# fan_2024-11-08_no1.net
KiCad netlist of a schematic drawn in EasyEDA Pro
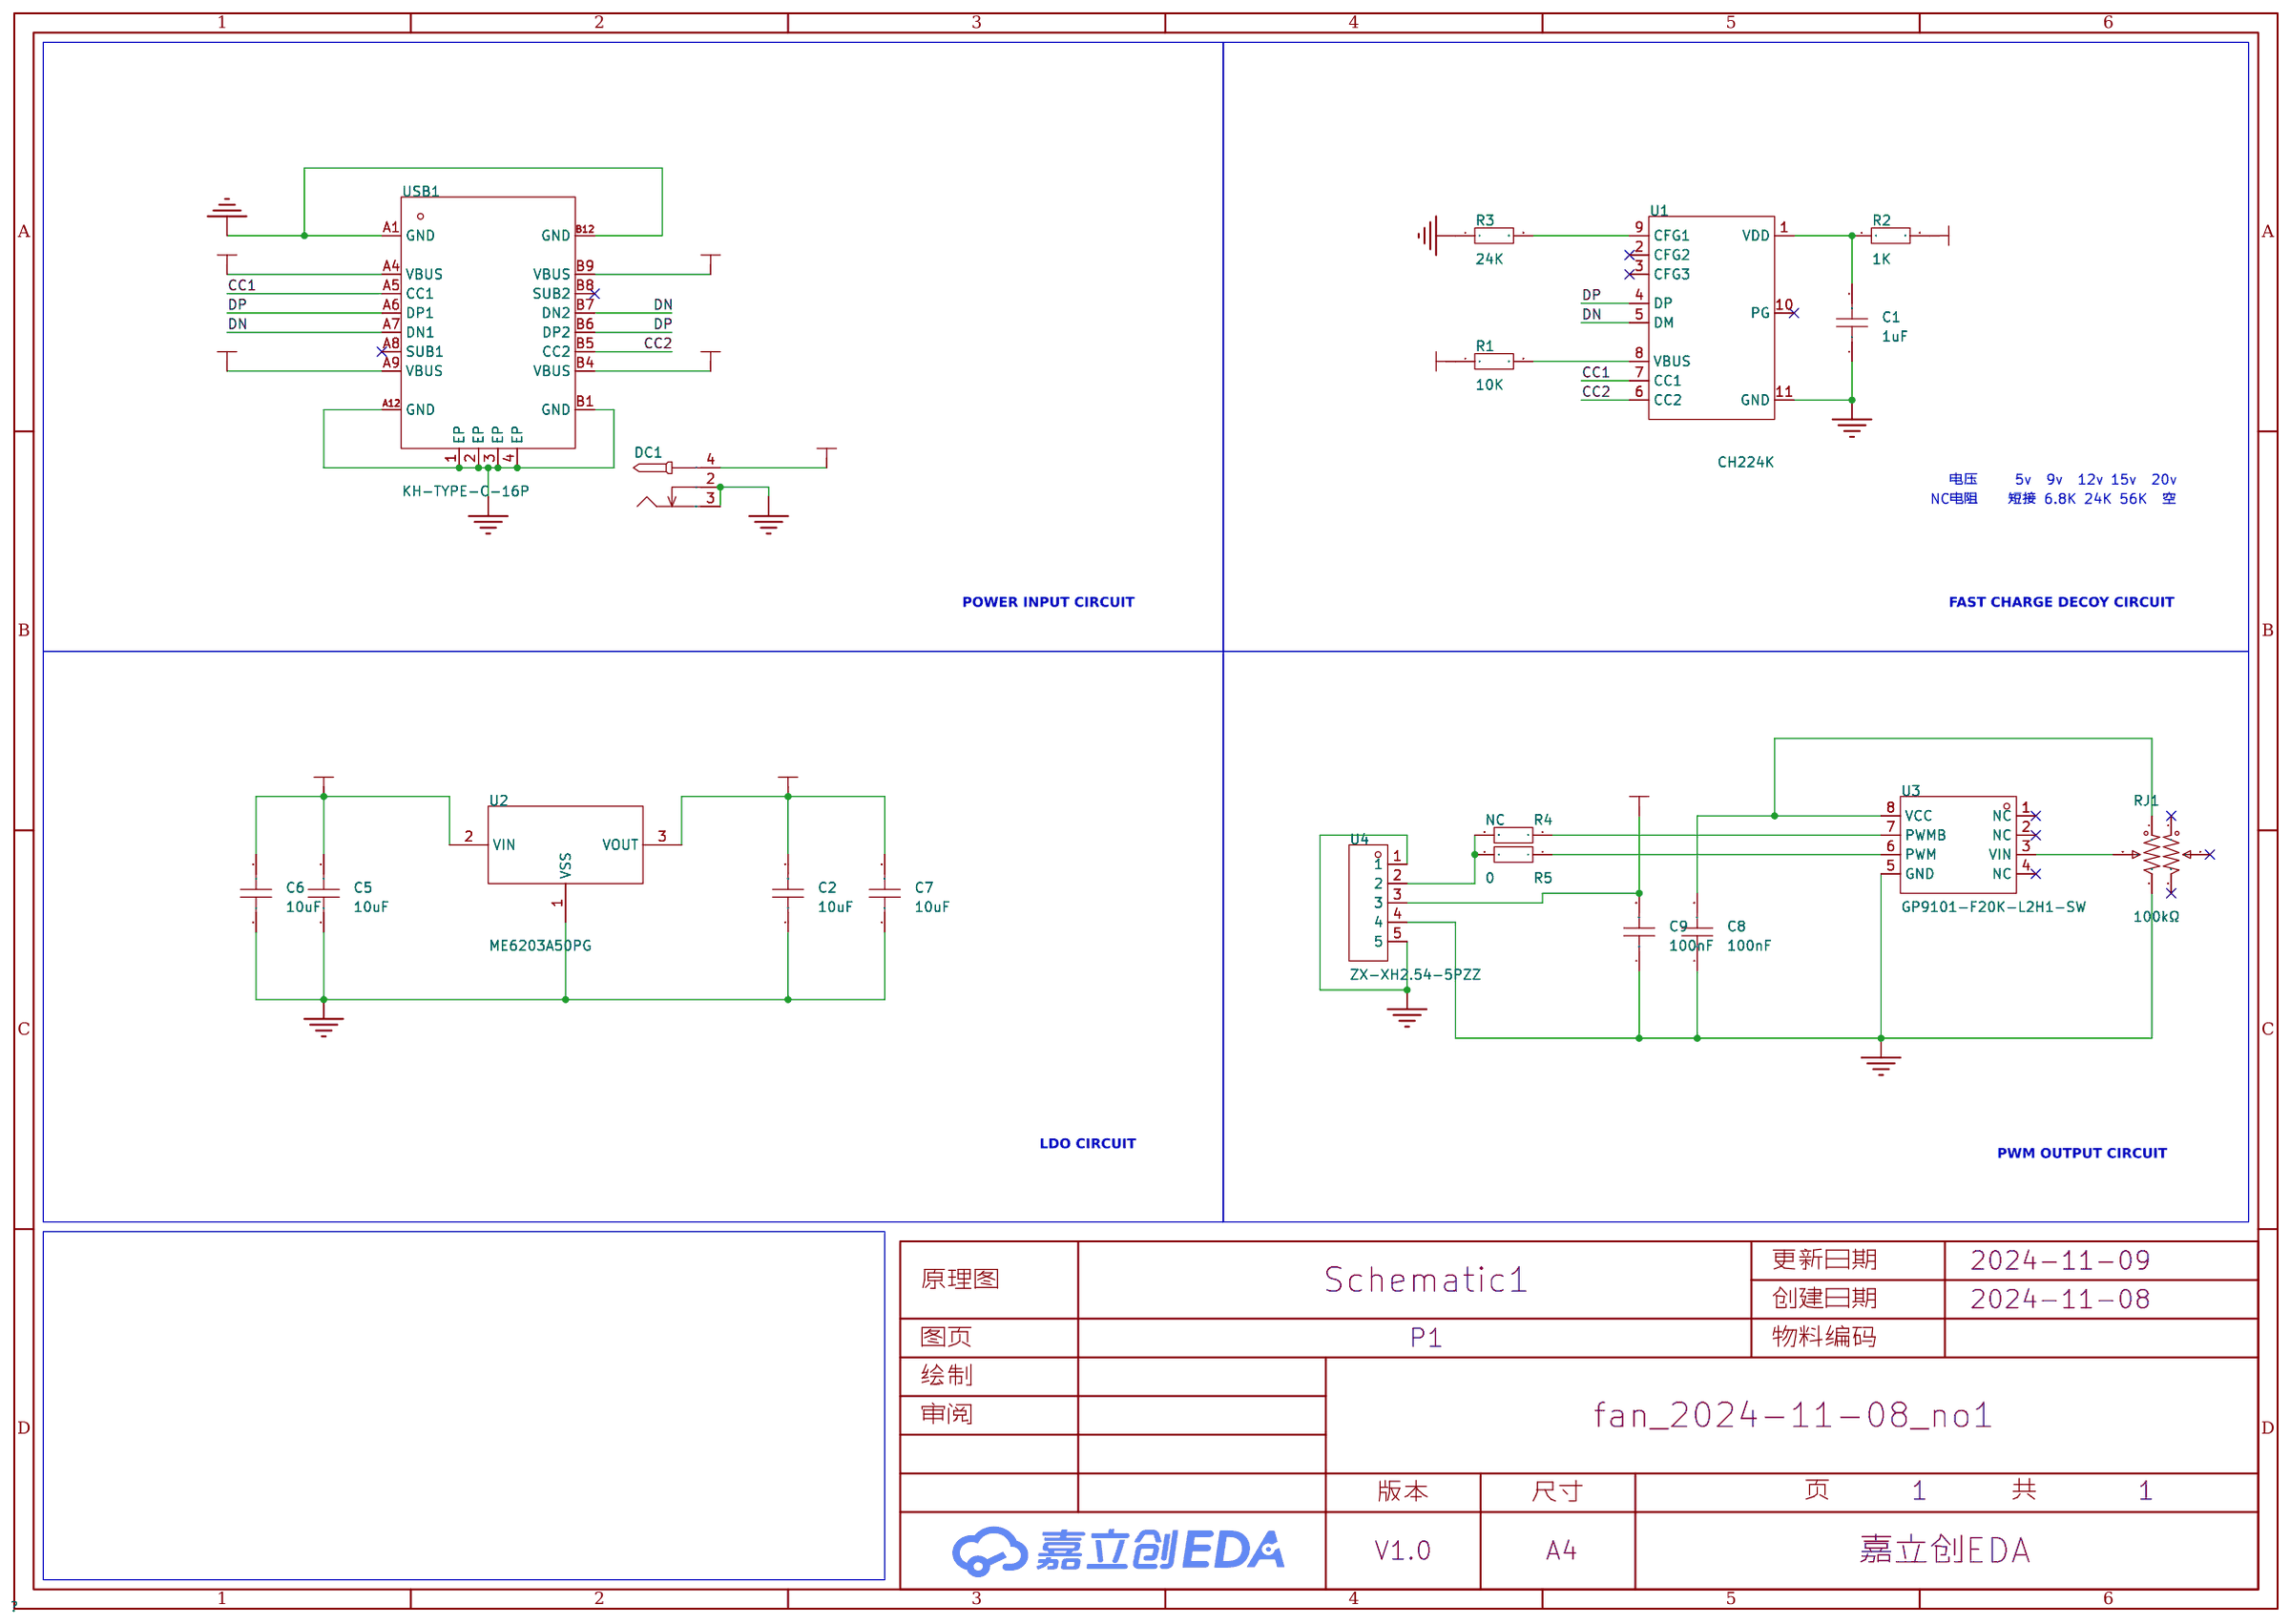
[diagram p0: schematic sheet]

(export (version "E")
  (design (tool "Eeschema 10.0.6"))
  (components
    (comp (ref "C1")
      (value "1uF")
      (footprint "easyedapro:C0603")
      (libsource (lib "easyedapro") (part "CapAcitance"))
    )
    (comp (ref "C2")
      (value "10uF")
      (footprint "easyedapro:C0603")
      (libsource (lib "easyedapro") (part "CapAcitance"))
    )
    (comp (ref "C5")
      (value "10uF")
      (footprint "easyedapro:C0603")
      (libsource (lib "easyedapro") (part "CapAcitance"))
    )
    (comp (ref "C6")
      (value "10uF")
      (footprint "easyedapro:C0603")
      (libsource (lib "easyedapro") (part "CapAcitance"))
    )
    (comp (ref "C7")
      (value "10uF")
      (footprint "easyedapro:C0603")
      (libsource (lib "easyedapro") (part "CapAcitance"))
    )
    (comp (ref "C8")
      (value "100nF")
      (footprint "easyedapro:C0603")
      (libsource (lib "easyedapro") (part "CapAcitance"))
    )
    (comp (ref "C9")
      (value "100nF")
      (footprint "easyedapro:C0603")
      (libsource (lib "easyedapro") (part "CapAcitance"))
    )
    (comp (ref "DC1")
      (value "~")
      (footprint "easyedapro:DC-2.0")
      (libsource (lib "easyedapro") (part "DC电源接口"))
    )
    (comp (ref "R1") (value "10K") (footprint "easyedapro:R1206") (libsource (lib "easyedapro") (part "电阻")))
    (comp (ref "R2") (value "1K") (footprint "easyedapro:R1206") (libsource (lib "easyedapro") (part "电阻")))
    (comp (ref "R3") (value "24K") (footprint "easyedapro:R1206") (libsource (lib "easyedapro") (part "电阻")))
    (comp (ref "R4") (value "NC") (footprint "easyedapro:R1206") (libsource (lib "easyedapro") (part "电阻")))
    (comp (ref "R5") (value "0") (footprint "easyedapro:R1206") (libsource (lib "easyedapro") (part "电阻")))
    (comp (ref "RJ1")
      (value "100kΩ")
      (footprint "easyedapro:RES-ADJ-TH_P092N-FC25CR100K")
      (description "阻值:100kΩ;精度:±20%;功率:25mW;")
      (fields
        (field (name "Manufacturer Part") "P092N-FC25CR100K")
        (field (name "Manufacturer") "TT Electronics")
      )
      (libsource (lib "easyedapro") (part "P092N-FC25CR100K"))
    )
    (comp (ref "U1")
      (value "CH224K")
      (footprint "easyedapro:ESSOP-10_L4.9-W3.9-P1.0-LS6.0-TL-EP")
      (description "应用功能:USB充电芯片;")
      (fields (field (name "Manufacturer") "WCH(南京沁恒)"))
      (libsource (lib "easyedapro") (part "CH224K"))
    )
    (comp (ref "U2")
      (value "ME6203A50PG")
      (footprint "easyedapro:SOT-89_L4.5-W2.5-P1.50-LS4.2-BR")
      (description "输出类型:固定;最大输入电压:30V;输出电压:5V;最大输出电流:100mA;电源纹波抑制比(PSRR):40dB@(1kHz);输出极性:正极;")
      (fields (field (name "Manufacturer") "MICRONE(南京微盟)"))
      (libsource (lib "easyedapro") (part "ME6203A50PG"))
    )
    (comp (ref "U3")
      (value "GP9101-F20K-L2H1-SW")
      (footprint "easyedapro:SOP-8_L5.0-W3.9-P1.27-LS6.0-BL")
      (fields (field (name "Manufacturer") "Guestgood(客益)"))
      (libsource (lib "easyedapro") (part "GP9101-F20K-L2H1-SW"))
    )
    (comp (ref "U4")
      (value "ZX-XH2.54-5PZZ")
      (footprint "easyedapro:CONN-TH_5P-P2.50_ZX-XH2.54-5PZZ")
      (fields (field (name "Manufacturer") "Megastar(兆星)"))
      (libsource (lib "easyedapro") (part "ZX-XH2.54-5PZZ"))
    )
    (comp (ref "USB1")
      (value "KH-TYPE-C-16P")
      (footprint "easyedapro:USB-C-SMD_KH-TYPE-C-16P")
      (description "连接器类型:Type-C;标准:-;公母:母;端口数量:1;触点数量:16P;安装方式:卧贴;额定电流 - 电源:3A;工作温度范围:-40°C~+85°C;")
      (fields (field (name "Manufacturer") "kinghelm(金航标)"))
      (libsource (lib "easyedapro") (part "KH-TYPE-C-16P"))
    )
  )
  (nets
    (net (code "1") (name "+5V") (class "Default")
      (node (ref "C2") (pin "2") (pinfunction "2_2") (pintype "input"))
      (node (ref "C7") (pin "2") (pinfunction "2_2") (pintype "input"))
      (node (ref "U2") (pin "3") (pinfunction "VOUT_3") (pintype "unspecified"))
    )
    (net (code "2") (name "+12V") (class "Default")
      (node (ref "C5") (pin "2") (pinfunction "2_2") (pintype "input"))
      (node (ref "C6") (pin "2") (pinfunction "2_2") (pintype "input"))
      (node (ref "C9") (pin "2") (pinfunction "2_2") (pintype "input"))
      (node (ref "U2") (pin "2") (pinfunction "VIN_2") (pintype "unspecified"))
      (node (ref "U4") (pin "3") (pinfunction "3_3") (pintype "unspecified"))
    )
    (net (code "3") (name "/CC1") (class "Default")
      (node (ref "U1") (pin "7") (pinfunction "CC1_7") (pintype "unspecified"))
      (node (ref "USB1") (pin "A5") (pinfunction "CC1_A5") (pintype "unspecified"))
    )
    (net (code "4") (name "/CC2") (class "Default")
      (node (ref "U1") (pin "6") (pinfunction "CC2_6") (pintype "unspecified"))
      (node (ref "USB1") (pin "B5") (pinfunction "CC2_B5") (pintype "unspecified"))
    )
    (net (code "5") (name "/DN") (class "Default")
      (node (ref "U1") (pin "5") (pinfunction "DM_5") (pintype "unspecified"))
      (node (ref "USB1") (pin "A7") (pinfunction "DN1_A7") (pintype "unspecified"))
      (node (ref "USB1") (pin "B7") (pinfunction "DN2_B7") (pintype "unspecified"))
    )
    (net (code "6") (name "/DP") (class "Default")
      (node (ref "U1") (pin "4") (pinfunction "DP_4") (pintype "unspecified"))
      (node (ref "USB1") (pin "A6") (pinfunction "DP1_A6") (pintype "unspecified"))
      (node (ref "USB1") (pin "B6") (pinfunction "DP2_B6") (pintype "unspecified"))
    )
    (net (code "7") (name "GND") (class "Default")
      (node (ref "C1") (pin "1") (pinfunction "1_1") (pintype "input"))
      (node (ref "C2") (pin "1") (pinfunction "1_1") (pintype "input"))
      (node (ref "C5") (pin "1") (pinfunction "1_1") (pintype "input"))
      (node (ref "C6") (pin "1") (pinfunction "1_1") (pintype "input"))
      (node (ref "C7") (pin "1") (pinfunction "1_1") (pintype "input"))
      (node (ref "C8") (pin "1") (pinfunction "1_1") (pintype "input"))
      (node (ref "C9") (pin "1") (pinfunction "1_1") (pintype "input"))
      (node (ref "DC1") (pin "2") (pinfunction "2_2") (pintype "input"))
      (node (ref "DC1") (pin "3") (pinfunction "3_3") (pintype "input"))
      (node (ref "R3") (pin "1") (pinfunction "1_1") (pintype "input"))
      (node (ref "RJ1") (pin "6") (pinfunction "6_6") (pintype "unspecified"))
      (node (ref "U1") (pin "11") (pinfunction "GND_11") (pintype "unspecified"))
      (node (ref "U2") (pin "1") (pinfunction "VSS_1") (pintype "unspecified"))
      (node (ref "U3") (pin "5") (pinfunction "GND_5") (pintype "unspecified"))
      (node (ref "U4") (pin "1") (pinfunction "1_1") (pintype "unspecified"))
      (node (ref "U4") (pin "4") (pinfunction "4_4") (pintype "unspecified"))
      (node (ref "U4") (pin "5") (pinfunction "5_5") (pintype "unspecified"))
      (node (ref "USB1") (pin "1") (pinfunction "EP_1") (pintype "unspecified"))
      (node (ref "USB1") (pin "2") (pinfunction "EP_2") (pintype "unspecified"))
      (node (ref "USB1") (pin "3") (pinfunction "EP_3") (pintype "unspecified"))
      (node (ref "USB1") (pin "4") (pinfunction "EP_4") (pintype "unspecified"))
      (node (ref "USB1") (pin "A1") (pinfunction "GND_A1") (pintype "unspecified"))
      (node (ref "USB1") (pin "A12") (pinfunction "GND_A12") (pintype "unspecified"))
      (node (ref "USB1") (pin "B1") (pinfunction "GND_B1") (pintype "unspecified"))
      (node (ref "USB1") (pin "B12") (pinfunction "GND_B12") (pintype "unspecified"))
    )
    (net (code "8") (name "Net-(R4-Pad2)") (class "Default")
      (node (ref "R4") (pin "2") (pinfunction "2_2") (pintype "input"))
      (node (ref "R5") (pin "2") (pinfunction "2_2") (pintype "input"))
      (node (ref "U4") (pin "2") (pinfunction "2_2") (pintype "unspecified"))
    )
    (net (code "9") (name "Net-(U1-CFG1)") (class "Default")
      (node (ref "R3") (pin "2") (pinfunction "2_2") (pintype "input"))
      (node (ref "U1") (pin "9") (pinfunction "CFG1_9") (pintype "unspecified"))
    )
    (net (code "10") (name "Net-(U1-VBUS)") (class "Default")
      (node (ref "R1") (pin "2") (pinfunction "2_2") (pintype "input"))
      (node (ref "U1") (pin "8") (pinfunction "VBUS_8") (pintype "unspecified"))
    )
    (net (code "11") (name "Net-(U1-VDD)") (class "Default")
      (node (ref "C1") (pin "2") (pinfunction "2_2") (pintype "input"))
      (node (ref "R2") (pin "1") (pinfunction "1_1") (pintype "input"))
      (node (ref "U1") (pin "1") (pinfunction "VDD_1") (pintype "unspecified"))
    )
    (net (code "12") (name "Net-(U3-PWM)") (class "Default")
      (node (ref "R5") (pin "1") (pinfunction "1_1") (pintype "input"))
      (node (ref "U3") (pin "6") (pinfunction "PWM_6") (pintype "unspecified"))
    )
    (net (code "13") (name "Net-(U3-PWMB)") (class "Default")
      (node (ref "R4") (pin "1") (pinfunction "1_1") (pintype "input"))
      (node (ref "U3") (pin "7") (pinfunction "PWMB_7") (pintype "unspecified"))
    )
    (net (code "14") (name "Net-(U3-VCC)") (class "Default")
      (node (ref "C8") (pin "2") (pinfunction "2_2") (pintype "input"))
      (node (ref "RJ1") (pin "4") (pinfunction "4_4") (pintype "unspecified"))
      (node (ref "U3") (pin "8") (pinfunction "VCC_8") (pintype "unspecified"))
    )
    (net (code "15") (name "Net-(U3-VIN)") (class "Default")
      (node (ref "RJ1") (pin "5") (pinfunction "5_5") (pintype "unspecified"))
      (node (ref "U3") (pin "3") (pinfunction "VIN_3") (pintype "unspecified"))
    )
    (net (code "16") (name "VBUS") (class "Default")
      (node (ref "DC1") (pin "4") (pinfunction "4_4") (pintype "input"))
      (node (ref "R1") (pin "1") (pinfunction "1_1") (pintype "input"))
      (node (ref "R2") (pin "2") (pinfunction "2_2") (pintype "input"))
      (node (ref "USB1") (pin "A4") (pinfunction "VBUS_A4") (pintype "unspecified"))
      (node (ref "USB1") (pin "A9") (pinfunction "VBUS_A9") (pintype "unspecified"))
      (node (ref "USB1") (pin "B4") (pinfunction "VBUS_B4") (pintype "unspecified"))
      (node (ref "USB1") (pin "B9") (pinfunction "VBUS_B9") (pintype "unspecified"))
    )
    (net (code "17") (name "unconnected-(RJ1-Pad1)") (class "Default")
      (node (ref "RJ1") (pin "1") (pinfunction "1_1") (pintype "unspecified+no_connect"))
    )
    (net (code "18") (name "unconnected-(RJ1-Pad2)") (class "Default")
      (node (ref "RJ1") (pin "2") (pinfunction "2_2") (pintype "unspecified+no_connect"))
    )
    (net (code "19") (name "unconnected-(RJ1-Pad3)") (class "Default")
      (node (ref "RJ1") (pin "3") (pinfunction "3_3") (pintype "unspecified+no_connect"))
    )
    (net (code "20") (name "unconnected-(U1-CFG2-Pad2)") (class "Default")
      (node (ref "U1") (pin "2") (pinfunction "CFG2_2") (pintype "unspecified+no_connect"))
    )
    (net (code "21") (name "unconnected-(U1-CFG3-Pad3)") (class "Default")
      (node (ref "U1") (pin "3") (pinfunction "CFG3_3") (pintype "unspecified+no_connect"))
    )
    (net (code "22") (name "unconnected-(U1-PG-Pad10)") (class "Default")
      (node (ref "U1") (pin "10") (pinfunction "PG_10") (pintype "unspecified+no_connect"))
    )
    (net (code "23") (name "unconnected-(U3-NC-Pad1)") (class "Default")
      (node (ref "U3") (pin "1") (pinfunction "NC_1") (pintype "unspecified+no_connect"))
    )
    (net (code "24") (name "unconnected-(U3-NC-Pad2)") (class "Default")
      (node (ref "U3") (pin "2") (pinfunction "NC_2") (pintype "unspecified+no_connect"))
    )
    (net (code "25") (name "unconnected-(U3-NC-Pad4)") (class "Default")
      (node (ref "U3") (pin "4") (pinfunction "NC_4") (pintype "unspecified+no_connect"))
    )
    (net (code "26") (name "unconnected-(USB1-SUB1-PadA8)") (class "Default")
      (node (ref "USB1") (pin "A8") (pinfunction "SUB1_A8") (pintype "unspecified+no_connect"))
    )
    (net (code "27") (name "unconnected-(USB1-SUB2-PadB8)") (class "Default")
      (node (ref "USB1") (pin "B8") (pinfunction "SUB2_B8") (pintype "unspecified+no_connect"))
    )
  )
)
